# LEDDriver.net
KiCad netlist of a schematic drawn in EAGLE
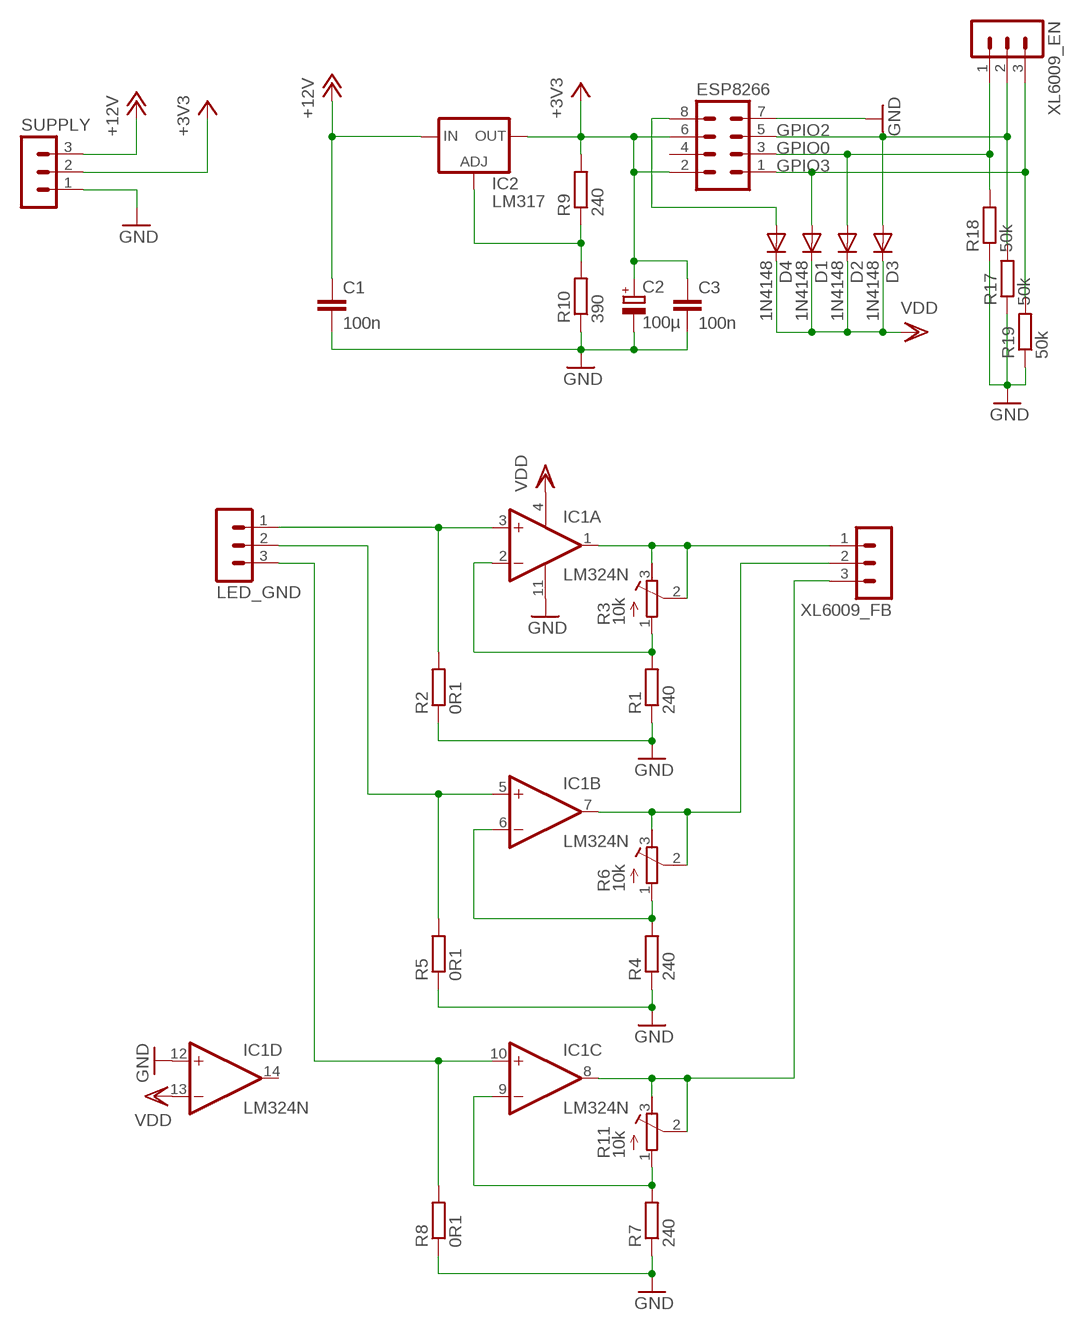
[diagram p0: schematic, sheet 1]

(export (version "E")
  (design (tool "Eeschema 10.0.6"))
  (components
    (comp (ref "C1")
      (value "100n")
      (footprint "eagle-import:C075-032X103")
      (libsource (lib "eagle-import") (part "C-EU075-032X103"))
    )
    (comp (ref "C2")
      (value "100µ")
      (footprint "eagle-import:E5-8,5")
      (libsource (lib "eagle-import") (part "CPOL-EUE5-8.5"))
    )
    (comp (ref "C3")
      (value "100n")
      (footprint "eagle-import:C075-032X103")
      (libsource (lib "eagle-import") (part "C-EU075-032X103"))
    )
    (comp (ref "D1")
      (value "1N4148")
      (footprint "eagle-import:D-2.5")
      (libsource (lib "eagle-import") (part "DIODE-D-2.5"))
    )
    (comp (ref "D2")
      (value "1N4148")
      (footprint "eagle-import:D-2.5")
      (libsource (lib "eagle-import") (part "DIODE-D-2.5"))
    )
    (comp (ref "D3")
      (value "1N4148")
      (footprint "eagle-import:D-2.5")
      (libsource (lib "eagle-import") (part "DIODE-D-2.5"))
    )
    (comp (ref "D4")
      (value "1N4148")
      (footprint "eagle-import:D-2.5")
      (libsource (lib "eagle-import") (part "DIODE-D-2.5"))
    )
    (comp (ref "ESP8266")
      (value "MA04-2")
      (footprint "eagle-import:MA04-2")
      (libsource (lib "eagle-import") (part "MA04-2"))
    )
    (comp (ref "IC1")
      (value "LM324N")
      (footprint "eagle-import:DIL14")
      (libsource (lib "eagle-import") (part "LM324N"))
    )
    (comp (ref "IC2")
      (value "LM317")
      (footprint "eagle-import:317TS")
      (libsource (lib "eagle-import") (part "LM317TS"))
    )
    (comp (ref "LED_GND")
      (value "MA03-1")
      (footprint "eagle-import:MA03-1")
      (libsource (lib "eagle-import") (part "MA03-1"))
    )
    (comp (ref "R1")
      (value "240")
      (footprint "eagle-import:0204V")
      (libsource (lib "eagle-import") (part "R-EU_0204/2V"))
    )
    (comp (ref "R2")
      (value "0R1")
      (footprint "eagle-import:0204V")
      (libsource (lib "eagle-import") (part "R-EU_0204/2V"))
    )
    (comp (ref "R3")
      (value "10k")
      (footprint "eagle-import:RTRIM64W")
      (libsource (lib "eagle-import") (part "R-TRIMM64W"))
    )
    (comp (ref "R4")
      (value "240")
      (footprint "eagle-import:0204V")
      (libsource (lib "eagle-import") (part "R-EU_0204/2V"))
    )
    (comp (ref "R5")
      (value "0R1")
      (footprint "eagle-import:0204V")
      (libsource (lib "eagle-import") (part "R-EU_0204/2V"))
    )
    (comp (ref "R6")
      (value "10k")
      (footprint "eagle-import:RTRIM64W")
      (libsource (lib "eagle-import") (part "R-TRIMM64W"))
    )
    (comp (ref "R7")
      (value "240")
      (footprint "eagle-import:0204V")
      (libsource (lib "eagle-import") (part "R-EU_0204/2V"))
    )
    (comp (ref "R8")
      (value "0R1")
      (footprint "eagle-import:0204V")
      (libsource (lib "eagle-import") (part "R-EU_0204/2V"))
    )
    (comp (ref "R9")
      (value "240")
      (footprint "eagle-import:0204V")
      (libsource (lib "eagle-import") (part "R-EU_0204/2V"))
    )
    (comp (ref "R10")
      (value "390")
      (footprint "eagle-import:0207_12")
      (libsource (lib "eagle-import") (part "R-EU_0207/12"))
    )
    (comp (ref "R11")
      (value "10k")
      (footprint "eagle-import:RTRIM64W")
      (libsource (lib "eagle-import") (part "R-TRIMM64W"))
    )
    (comp (ref "R17")
      (value "50k")
      (footprint "eagle-import:0207_12")
      (libsource (lib "eagle-import") (part "R-EU_0207/12"))
    )
    (comp (ref "R18")
      (value "50k")
      (footprint "eagle-import:0207_12")
      (libsource (lib "eagle-import") (part "R-EU_0207/12"))
    )
    (comp (ref "R19")
      (value "50k")
      (footprint "eagle-import:0207_12")
      (libsource (lib "eagle-import") (part "R-EU_0207/12"))
    )
    (comp (ref "SUPPLY")
      (value "MA03-1")
      (footprint "eagle-import:MA03-1")
      (libsource (lib "eagle-import") (part "MA03-1"))
    )
    (comp (ref "XL6009_EN")
      (value "MA03-1")
      (footprint "eagle-import:MA03-1")
      (libsource (lib "eagle-import") (part "MA03-1"))
    )
    (comp (ref "XL6009_FB")
      (value "MA03-1")
      (footprint "eagle-import:MA03-1")
      (libsource (lib "eagle-import") (part "MA03-1"))
    )
  )
  (nets
    (net (code "1") (name "+3V3") (class "Default")
      (node (ref "C2") (pin "+") (pinfunction "+_+") (pintype "passive"))
      (node (ref "C3") (pin "1") (pinfunction "1_1") (pintype "passive"))
      (node (ref "ESP8266") (pin "2") (pinfunction "2_2") (pintype "passive"))
      (node (ref "ESP8266") (pin "6") (pinfunction "6_6") (pintype "passive"))
      (node (ref "IC2") (pin "2") (pinfunction "OUT_2") (pintype "passive"))
      (node (ref "R9") (pin "2") (pinfunction "2_2") (pintype "passive"))
      (node (ref "SUPPLY") (pin "2") (pinfunction "2_2") (pintype "passive"))
    )
    (net (code "2") (name "+12V") (class "Default")
      (node (ref "C1") (pin "1") (pinfunction "1_1") (pintype "passive"))
      (node (ref "IC2") (pin "3") (pinfunction "IN_3") (pintype "input"))
      (node (ref "SUPPLY") (pin "3") (pinfunction "3_3") (pintype "passive"))
    )
    (net (code "3") (name "/GPIO0") (class "Default")
      (node (ref "D2") (pin "A") (pinfunction "A_A") (pintype "passive"))
      (node (ref "ESP8266") (pin "3") (pinfunction "3_3") (pintype "passive"))
      (node (ref "R18") (pin "2") (pinfunction "2_2") (pintype "passive"))
      (node (ref "XL6009_EN") (pin "1") (pinfunction "1_1") (pintype "passive"))
    )
    (net (code "4") (name "/GPIO2") (class "Default")
      (node (ref "D3") (pin "A") (pinfunction "A_A") (pintype "passive"))
      (node (ref "ESP8266") (pin "5") (pinfunction "5_5") (pintype "passive"))
      (node (ref "R17") (pin "2") (pinfunction "2_2") (pintype "passive"))
      (node (ref "XL6009_EN") (pin "2") (pinfunction "2_2") (pintype "passive"))
    )
    (net (code "5") (name "/GPIO3") (class "Default")
      (node (ref "D1") (pin "A") (pinfunction "A_A") (pintype "passive"))
      (node (ref "ESP8266") (pin "1") (pinfunction "1_1") (pintype "passive"))
      (node (ref "R19") (pin "2") (pinfunction "2_2") (pintype "passive"))
      (node (ref "XL6009_EN") (pin "3") (pinfunction "3_3") (pintype "passive"))
    )
    (net (code "6") (name "GND") (class "Default")
      (node (ref "C1") (pin "2") (pinfunction "2_2") (pintype "passive"))
      (node (ref "C2") (pin "-") (pinfunction "-_-") (pintype "passive"))
      (node (ref "C3") (pin "2") (pinfunction "2_2") (pintype "passive"))
      (node (ref "ESP8266") (pin "7") (pinfunction "7_7") (pintype "passive"))
      (node (ref "IC1") (pin "11") (pinfunction "V-_11") (pintype "power_in"))
      (node (ref "IC1") (pin "12") (pinfunction "+IN_12") (pintype "input"))
      (node (ref "R1") (pin "1") (pinfunction "1_1") (pintype "passive"))
      (node (ref "R10") (pin "1") (pinfunction "1_1") (pintype "passive"))
      (node (ref "R17") (pin "1") (pinfunction "1_1") (pintype "passive"))
      (node (ref "R18") (pin "1") (pinfunction "1_1") (pintype "passive"))
      (node (ref "R19") (pin "1") (pinfunction "1_1") (pintype "passive"))
      (node (ref "R2") (pin "1") (pinfunction "1_1") (pintype "passive"))
      (node (ref "R4") (pin "1") (pinfunction "1_1") (pintype "passive"))
      (node (ref "R5") (pin "1") (pinfunction "1_1") (pintype "passive"))
      (node (ref "R7") (pin "1") (pinfunction "1_1") (pintype "passive"))
      (node (ref "R8") (pin "1") (pinfunction "1_1") (pintype "passive"))
      (node (ref "SUPPLY") (pin "1") (pinfunction "1_1") (pintype "passive"))
    )
    (net (code "7") (name "Net-(D4-PadA)") (class "Default")
      (node (ref "D4") (pin "A") (pinfunction "A_A") (pintype "passive"))
      (node (ref "ESP8266") (pin "8") (pinfunction "8_8") (pintype "passive"))
    )
    (net (code "8") (name "Net-(IC1A-+IN)") (class "Default")
      (node (ref "IC1") (pin "3") (pinfunction "+IN_3") (pintype "input"))
      (node (ref "LED_GND") (pin "1") (pinfunction "1_1") (pintype "passive"))
      (node (ref "R2") (pin "2") (pinfunction "2_2") (pintype "passive"))
    )
    (net (code "9") (name "Net-(IC1A--IN)") (class "Default")
      (node (ref "IC1") (pin "2") (pinfunction "-IN_2") (pintype "input"))
      (node (ref "R1") (pin "2") (pinfunction "2_2") (pintype "passive"))
      (node (ref "R3") (pin "1") (pinfunction "A_1") (pintype "passive"))
    )
    (net (code "10") (name "Net-(IC1A-OUT)") (class "Default")
      (node (ref "IC1") (pin "1") (pinfunction "OUT_1") (pintype "output"))
      (node (ref "R3") (pin "2") (pinfunction "S_2") (pintype "passive"))
      (node (ref "R3") (pin "3") (pinfunction "E_3") (pintype "passive"))
      (node (ref "XL6009_FB") (pin "1") (pinfunction "1_1") (pintype "passive"))
    )
    (net (code "11") (name "Net-(IC1B-+IN)") (class "Default")
      (node (ref "IC1") (pin "5") (pinfunction "+IN_5") (pintype "input"))
      (node (ref "LED_GND") (pin "2") (pinfunction "2_2") (pintype "passive"))
      (node (ref "R5") (pin "2") (pinfunction "2_2") (pintype "passive"))
    )
    (net (code "12") (name "Net-(IC1B--IN)") (class "Default")
      (node (ref "IC1") (pin "6") (pinfunction "-IN_6") (pintype "input"))
      (node (ref "R4") (pin "2") (pinfunction "2_2") (pintype "passive"))
      (node (ref "R6") (pin "1") (pinfunction "A_1") (pintype "passive"))
    )
    (net (code "13") (name "Net-(IC1B-OUT)") (class "Default")
      (node (ref "IC1") (pin "7") (pinfunction "OUT_7") (pintype "output"))
      (node (ref "R6") (pin "2") (pinfunction "S_2") (pintype "passive"))
      (node (ref "R6") (pin "3") (pinfunction "E_3") (pintype "passive"))
      (node (ref "XL6009_FB") (pin "2") (pinfunction "2_2") (pintype "passive"))
    )
    (net (code "14") (name "Net-(IC1C-+IN)") (class "Default")
      (node (ref "IC1") (pin "10") (pinfunction "+IN_10") (pintype "input"))
      (node (ref "LED_GND") (pin "3") (pinfunction "3_3") (pintype "passive"))
      (node (ref "R8") (pin "2") (pinfunction "2_2") (pintype "passive"))
    )
    (net (code "15") (name "Net-(IC1C--IN)") (class "Default")
      (node (ref "IC1") (pin "9") (pinfunction "-IN_9") (pintype "input"))
      (node (ref "R11") (pin "1") (pinfunction "A_1") (pintype "passive"))
      (node (ref "R7") (pin "2") (pinfunction "2_2") (pintype "passive"))
    )
    (net (code "16") (name "Net-(IC1C-OUT)") (class "Default")
      (node (ref "IC1") (pin "8") (pinfunction "OUT_8") (pintype "output"))
      (node (ref "R11") (pin "2") (pinfunction "S_2") (pintype "passive"))
      (node (ref "R11") (pin "3") (pinfunction "E_3") (pintype "passive"))
      (node (ref "XL6009_FB") (pin "3") (pinfunction "3_3") (pintype "passive"))
    )
    (net (code "17") (name "Net-(IC2-ADJ)") (class "Default")
      (node (ref "IC2") (pin "1") (pinfunction "ADJ_1") (pintype "input"))
      (node (ref "R10") (pin "2") (pinfunction "2_2") (pintype "passive"))
      (node (ref "R9") (pin "1") (pinfunction "1_1") (pintype "passive"))
    )
    (net (code "18") (name "VDD") (class "Default")
      (node (ref "D1") (pin "C") (pinfunction "C_C") (pintype "passive"))
      (node (ref "D2") (pin "C") (pinfunction "C_C") (pintype "passive"))
      (node (ref "D3") (pin "C") (pinfunction "C_C") (pintype "passive"))
      (node (ref "D4") (pin "C") (pinfunction "C_C") (pintype "passive"))
      (node (ref "IC1") (pin "13") (pinfunction "-IN_13") (pintype "input"))
      (node (ref "IC1") (pin "4") (pinfunction "V+_4") (pintype "power_in"))
    )
    (net (code "19") (name "unconnected-(ESP8266-Pad4)") (class "Default")
      (node (ref "ESP8266") (pin "4") (pinfunction "4_4") (pintype "passive"))
    )
    (net (code "20") (name "unconnected-(IC1D-OUT-Pad14)") (class "Default")
      (node (ref "IC1") (pin "14") (pinfunction "OUT_14") (pintype "output"))
    )
  )
)
